# Strain_gauge.net
KiCad netlist of a schematic drawn in EAGLE
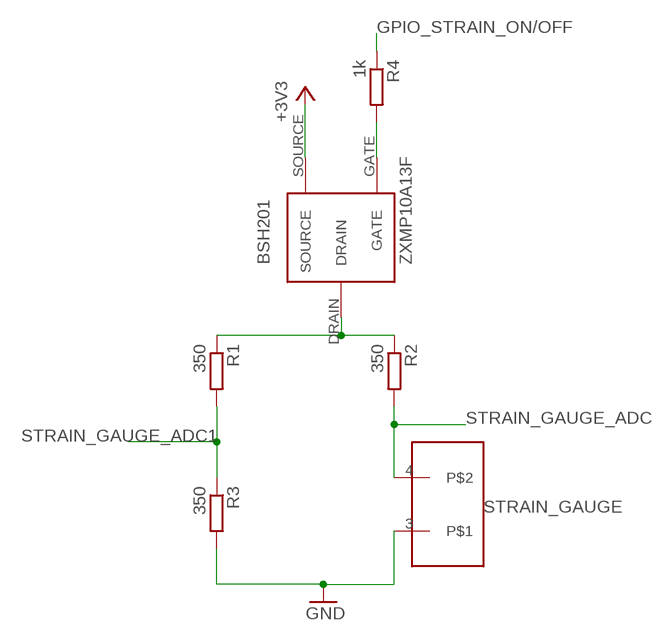
[diagram p0: schematic, sheet 1]

(export (version "E")
  (design (tool "Eeschema 10.0.6"))
  (components
    (comp (ref "BSH201")
      (value "ZXMP10A13F")
      (footprint "eagle-import:P-CHANNEL")
      (libsource (lib "eagle-import") (part "ZXMP10A13F"))
    )
    (comp (ref "R1")
      (value "350")
      (footprint "eagle-import:R0805")
      (libsource (lib "eagle-import") (part "R-EU_R0805"))
    )
    (comp (ref "R2")
      (value "350")
      (footprint "eagle-import:R0805")
      (libsource (lib "eagle-import") (part "R-EU_R0805"))
    )
    (comp (ref "R3")
      (value "350")
      (footprint "eagle-import:R0805")
      (libsource (lib "eagle-import") (part "R-EU_R0805"))
    )
    (comp (ref "R4")
      (value "1k")
      (footprint "eagle-import:R0805")
      (libsource (lib "eagle-import") (part "R-EU_R0805"))
    )
    (comp (ref "SKRUVPLINT_2P1")
      (value "SKRUVPLINT_2P")
      (footprint "eagle-import:SKRUVPLINT_2P")
      (libsource (lib "eagle-import") (part "SKRUVPLINT_2P"))
    )
  )
  (nets
    (net (code "1") (name "+3V3") (class "Default")
      (node (ref "BSH201") (pin "SOURCE") (pinfunction "SOURCE_SOURCE") (pintype "bidirectional"))
    )
    (net (code "2") (name "/GPIO_STRAIN_ON{slash}OFF") (class "Default")
      (node (ref "R4") (pin "1") (pinfunction "1_1") (pintype "passive"))
    )
    (net (code "3") (name "/STRAIN_GAUGE_ADC1") (class "Default")
      (node (ref "R1") (pin "2") (pinfunction "2_2") (pintype "passive"))
      (node (ref "R3") (pin "1") (pinfunction "1_1") (pintype "passive"))
    )
    (net (code "4") (name "/STRAIN_GAUGE_ADC2") (class "Default")
      (node (ref "R2") (pin "2") (pinfunction "2_2") (pintype "passive"))
      (node (ref "SKRUVPLINT_2P1") (pin "4") (pinfunction "P$2_4") (pintype "bidirectional"))
    )
    (net (code "5") (name "GND") (class "Default")
      (node (ref "R3") (pin "2") (pinfunction "2_2") (pintype "passive"))
      (node (ref "SKRUVPLINT_2P1") (pin "3") (pinfunction "P$1_3") (pintype "bidirectional"))
    )
    (net (code "6") (name "Net-(BSH201-PadDRAIN)") (class "Default")
      (node (ref "BSH201") (pin "DRAIN") (pinfunction "DRAIN_DRAIN") (pintype "bidirectional"))
      (node (ref "R1") (pin "1") (pinfunction "1_1") (pintype "passive"))
      (node (ref "R2") (pin "1") (pinfunction "1_1") (pintype "passive"))
    )
    (net (code "7") (name "Net-(BSH201-PadGATE)") (class "Default")
      (node (ref "BSH201") (pin "GATE") (pinfunction "GATE_GATE") (pintype "bidirectional"))
      (node (ref "R4") (pin "2") (pinfunction "2_2") (pintype "passive"))
    )
  )
)
